# Slave_v2.net
KiCad netlist of a schematic drawn in Altium Designer
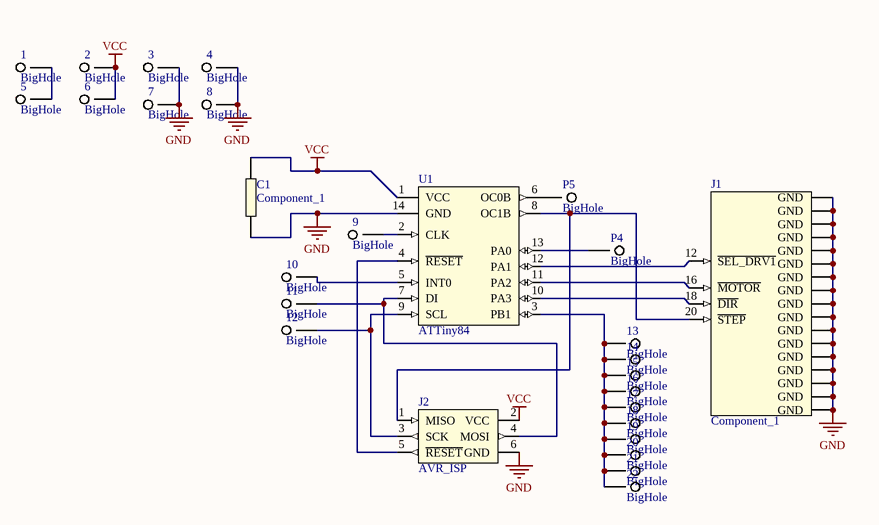
[diagram p0: Slave v2.SchDoc]

(export (version "E")
  (design (tool "Eeschema 10.0.6"))
  (components
    (comp (ref "1") (value "BigHole") (footprint "MEDHOLE") (libsource (lib "Pin") (part "BigHole")))
    (comp (ref "2") (value "BigHole") (footprint "MEDHOLE") (libsource (lib "Pin") (part "BigHole")))
    (comp (ref "3") (value "BigHole") (footprint "MEDHOLE") (libsource (lib "Pin") (part "BigHole")))
    (comp (ref "4") (value "BigHole") (footprint "MEDHOLE") (libsource (lib "Pin") (part "BigHole")))
    (comp (ref "5") (value "BigHole") (footprint "MEDHOLE") (libsource (lib "Pin") (part "BigHole")))
    (comp (ref "6") (value "BigHole") (footprint "MEDHOLE") (libsource (lib "Pin") (part "BigHole")))
    (comp (ref "7") (value "BigHole") (footprint "MEDHOLE") (libsource (lib "Pin") (part "BigHole")))
    (comp (ref "8") (value "BigHole") (footprint "MEDHOLE") (libsource (lib "Pin") (part "BigHole")))
    (comp (ref "9") (value "BigHole") (footprint "MEDHOLE") (libsource (lib "Pin") (part "BigHole")))
    (comp (ref "10") (value "BigHole") (footprint "MEDHOLE") (libsource (lib "Pin") (part "BigHole")))
    (comp (ref "11") (value "BigHole") (footprint "MEDHOLE") (libsource (lib "Pin") (part "BigHole")))
    (comp (ref "12") (value "BigHole") (footprint "MEDHOLE") (libsource (lib "Pin") (part "BigHole")))
    (comp (ref "13") (value "BigHole") (footprint "BigHole") (libsource (lib "Pin") (part "BigHole")))
    (comp (ref "14") (value "BigHole") (footprint "BigHole") (libsource (lib "Pin") (part "BigHole")))
    (comp (ref "15") (value "BigHole") (footprint "BigHole") (libsource (lib "Pin") (part "BigHole")))
    (comp (ref "16") (value "BigHole") (footprint "BigHole") (libsource (lib "Pin") (part "BigHole")))
    (comp (ref "17") (value "BigHole") (footprint "BigHole") (libsource (lib "Pin") (part "BigHole")))
    (comp (ref "18") (value "BigHole") (footprint "BigHole") (libsource (lib "Pin") (part "BigHole")))
    (comp (ref "19") (value "BigHole") (footprint "BigHole") (libsource (lib "Pin") (part "BigHole")))
    (comp (ref "20") (value "BigHole") (footprint "BigHole") (libsource (lib "Pin") (part "BigHole")))
    (comp (ref "21") (value "BigHole") (footprint "BigHole") (libsource (lib "Pin") (part "BigHole")))
    (comp (ref "22") (value "BigHole") (footprint "BigHole") (libsource (lib "Pin") (part "BigHole")))
    (comp (ref "C1")
      (value "Component_1")
      (footprint "200mil")
      (libsource (lib "anyComponent") (part "Component_1"))
    )
    (comp (ref "J1")
      (value "Component_1")
      (footprint "Header34")
      (libsource (lib "floppy") (part "Component_1"))
    )
    (comp (ref "J2") (value "AVR_ISP") (footprint "HEADER6") (libsource (lib "ISP") (part "AVR_ISP")))
    (comp (ref "P4") (value "BigHole") (footprint "MEDHOLE") (libsource (lib "Pin") (part "BigHole")))
    (comp (ref "P5") (value "BigHole") (footprint "MEDHOLE") (libsource (lib "Pin") (part "BigHole")))
    (comp (ref "U1") (value "ATTiny84") (footprint "DIP14") (libsource (lib "ATTiny84") (part "ATTiny84")))
  )
  (nets
    (net (code "1") (name "GND") (class "Default")
      (node (ref "3") (pin "1") (pinfunction "Pin?_1") (pintype "passive"))
      (node (ref "4") (pin "1") (pinfunction "Pin?_1") (pintype "passive"))
      (node (ref "7") (pin "1") (pinfunction "Pin?_1") (pintype "passive"))
      (node (ref "8") (pin "1") (pinfunction "Pin?_1") (pintype "passive"))
      (node (ref "C1") (pin "1") (pinfunction "1_1") (pintype "passive"))
      (node (ref "J1") (pin "1") (pinfunction "GND_1") (pintype "power_in"))
      (node (ref "J1") (pin "11") (pinfunction "GND_11") (pintype "power_in"))
      (node (ref "J1") (pin "13") (pinfunction "GND_13") (pintype "power_in"))
      (node (ref "J1") (pin "15") (pinfunction "GND_15") (pintype "power_in"))
      (node (ref "J1") (pin "17") (pinfunction "GND_17") (pintype "power_in"))
      (node (ref "J1") (pin "19") (pinfunction "GND_19") (pintype "power_in"))
      (node (ref "J1") (pin "21") (pinfunction "GND_21") (pintype "power_in"))
      (node (ref "J1") (pin "23") (pinfunction "GND_23") (pintype "power_in"))
      (node (ref "J1") (pin "25") (pinfunction "GND_25") (pintype "power_in"))
      (node (ref "J1") (pin "27") (pinfunction "GND_27") (pintype "power_in"))
      (node (ref "J1") (pin "29") (pinfunction "GND_29") (pintype "power_in"))
      (node (ref "J1") (pin "3") (pinfunction "GND_3") (pintype "power_in"))
      (node (ref "J1") (pin "31") (pinfunction "GND_31") (pintype "power_in"))
      (node (ref "J1") (pin "33") (pinfunction "GND_33") (pintype "power_in"))
      (node (ref "J1") (pin "5") (pinfunction "GND_5") (pintype "power_in"))
      (node (ref "J1") (pin "7") (pinfunction "GND_7") (pintype "power_in"))
      (node (ref "J1") (pin "9") (pinfunction "GND_9") (pintype "power_in"))
      (node (ref "J2") (pin "6") (pinfunction "GND_6") (pintype "power_in"))
      (node (ref "U1") (pin "14") (pinfunction "GND_14") (pintype "power_in"))
    )
    (net (code "2") (name "Net-(1-Pin?)") (class "Default")
      (node (ref "1") (pin "1") (pinfunction "Pin?_1") (pintype "passive"))
      (node (ref "5") (pin "1") (pinfunction "Pin?_1") (pintype "passive"))
    )
    (net (code "3") (name "Net-(9-Pin?)") (class "Default")
      (node (ref "9") (pin "1") (pinfunction "Pin?_1") (pintype "passive"))
      (node (ref "U1") (pin "2") (pinfunction "CLK_2") (pintype "input"))
    )
    (net (code "4") (name "Net-(10-Pin?)") (class "Default")
      (node (ref "10") (pin "1") (pinfunction "Pin?_1") (pintype "passive"))
      (node (ref "U1") (pin "5") (pinfunction "INT0_5") (pintype "input"))
    )
    (net (code "5") (name "Net-(11-Pin?)") (class "Default")
      (node (ref "11") (pin "1") (pinfunction "Pin?_1") (pintype "passive"))
      (node (ref "J2") (pin "4") (pinfunction "MOSI_4") (pintype "output"))
      (node (ref "U1") (pin "7") (pinfunction "DI_7") (pintype "input"))
    )
    (net (code "6") (name "Net-(12-Pin?)") (class "Default")
      (node (ref "12") (pin "1") (pinfunction "Pin?_1") (pintype "passive"))
      (node (ref "J2") (pin "3") (pinfunction "SCK_3") (pintype "output"))
      (node (ref "U1") (pin "9") (pinfunction "SCL_9") (pintype "input"))
    )
    (net (code "7") (name "Net-(13-Pin?)") (class "Default")
      (node (ref "13") (pin "1") (pinfunction "Pin?_1") (pintype "passive"))
      (node (ref "14") (pin "1") (pinfunction "Pin?_1") (pintype "passive"))
      (node (ref "15") (pin "1") (pinfunction "Pin?_1") (pintype "passive"))
      (node (ref "16") (pin "1") (pinfunction "Pin?_1") (pintype "passive"))
      (node (ref "17") (pin "1") (pinfunction "Pin?_1") (pintype "passive"))
      (node (ref "18") (pin "1") (pinfunction "Pin?_1") (pintype "passive"))
      (node (ref "19") (pin "1") (pinfunction "Pin?_1") (pintype "passive"))
      (node (ref "20") (pin "1") (pinfunction "Pin?_1") (pintype "passive"))
      (node (ref "21") (pin "1") (pinfunction "Pin?_1") (pintype "passive"))
      (node (ref "22") (pin "1") (pinfunction "Pin?_1") (pintype "passive"))
      (node (ref "U1") (pin "3") (pinfunction "PB1_3") (pintype "bidirectional"))
    )
    (net (code "8") (name "Net-(J1-~{DIR})") (class "Default")
      (node (ref "J1") (pin "18") (pinfunction "~{DIR}_18") (pintype "input"))
      (node (ref "U1") (pin "10") (pinfunction "PA3_10") (pintype "bidirectional"))
    )
    (net (code "9") (name "Net-(J1-~{MOTOR})") (class "Default")
      (node (ref "J1") (pin "16") (pinfunction "~{MOTOR}_16") (pintype "input"))
      (node (ref "U1") (pin "11") (pinfunction "PA2_11") (pintype "bidirectional"))
    )
    (net (code "10") (name "Net-(J1-~{SEL_DRV1})") (class "Default")
      (node (ref "J1") (pin "12") (pinfunction "~{SEL_DRV1}_12") (pintype "input"))
      (node (ref "U1") (pin "12") (pinfunction "PA1_12") (pintype "bidirectional"))
    )
    (net (code "11") (name "Net-(J1-~{STEP})") (class "Default")
      (node (ref "J1") (pin "20") (pinfunction "~{STEP}_20") (pintype "input"))
      (node (ref "J2") (pin "1") (pinfunction "MISO_1") (pintype "input"))
      (node (ref "U1") (pin "8") (pinfunction "OC1B_8") (pintype "output"))
    )
    (net (code "12") (name "Net-(J2-~{RESET})") (class "Default")
      (node (ref "J2") (pin "5") (pinfunction "~{RESET}_5") (pintype "output"))
      (node (ref "U1") (pin "4") (pinfunction "~{RESET}_4") (pintype "input"))
    )
    (net (code "13") (name "Net-(P4-Pin?)") (class "Default")
      (node (ref "P4") (pin "1") (pinfunction "Pin?_1") (pintype "passive"))
      (node (ref "U1") (pin "13") (pinfunction "PA0_13") (pintype "bidirectional"))
    )
    (net (code "14") (name "Net-(P5-Pin?)") (class "Default")
      (node (ref "P5") (pin "1") (pinfunction "Pin?_1") (pintype "passive"))
      (node (ref "U1") (pin "6") (pinfunction "OC0B_6") (pintype "output"))
    )
    (net (code "15") (name "VCC") (class "Default")
      (node (ref "2") (pin "1") (pinfunction "Pin?_1") (pintype "passive"))
      (node (ref "6") (pin "1") (pinfunction "Pin?_1") (pintype "passive"))
      (node (ref "C1") (pin "2") (pinfunction "2_2") (pintype "passive"))
      (node (ref "J2") (pin "2") (pinfunction "VCC_2") (pintype "power_in"))
      (node (ref "U1") (pin "1") (pinfunction "VCC_1") (pintype "power_in"))
    )
  )
)
